# Board_Power.net
KiCad netlist of a schematic drawn in Altium Designer
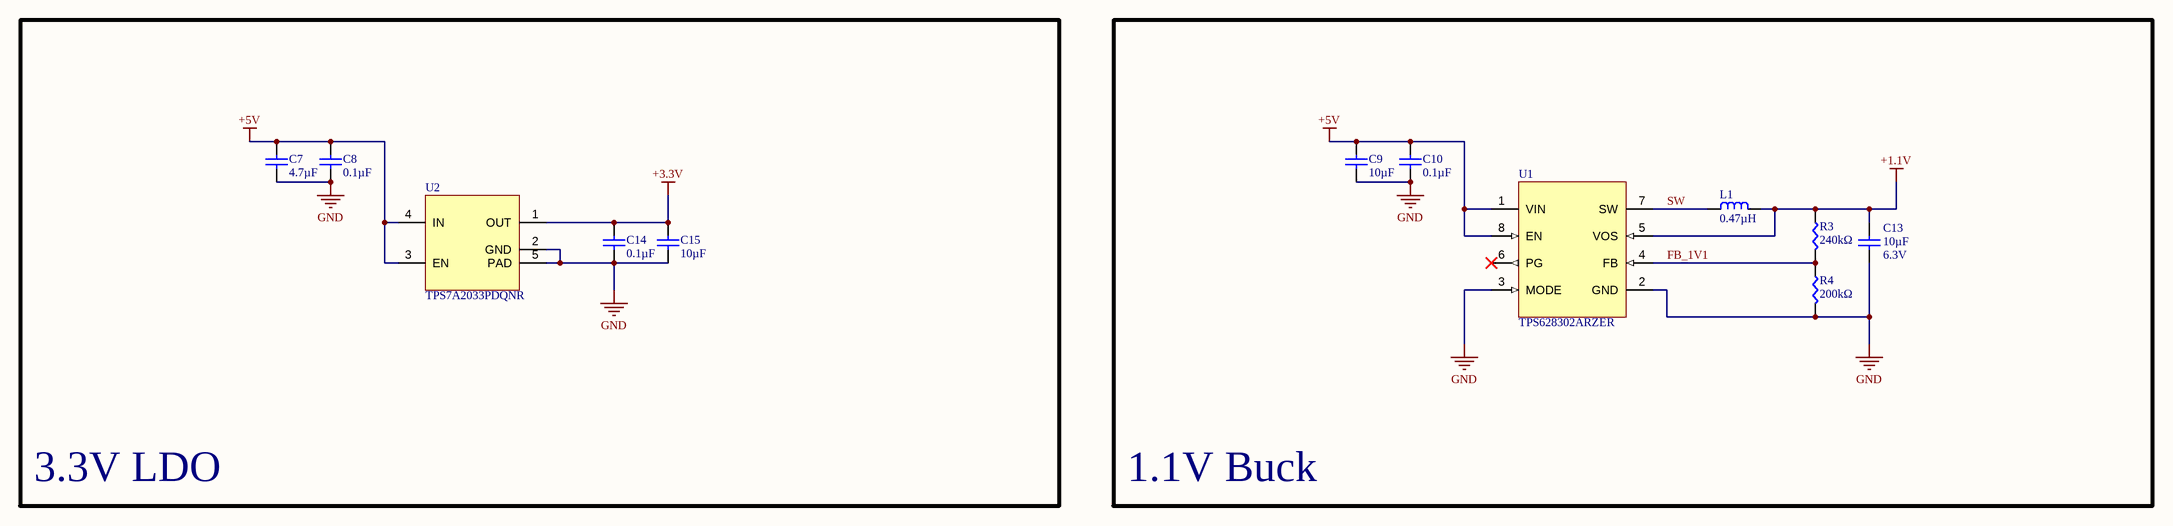
[diagram p0: Board_Power.SchDoc]

(export (version "E")
  (design (tool "Eeschema 10.0.6"))
  (components
    (comp (ref "C7")
      (value "4.7µF")
      (footprint "CAP0603")
      (description "4.7 µF ±10% 25V Ceramic Capacitor X5R 0603 (1608 Metric)")
      (fields (field (name "VOLTAGE") "25V") (field (name "Comment") "GRT21BR61H475KE13L"))
      (libsource (lib "Schlib1") (part "GRM188R61E475KE11D"))
    )
    (comp (ref "C8")
      (value "0.1µF")
      (footprint "CAP0402")
      (description "0.1 µF ±10% 50V Ceramic Capacitor X5R 0402 (1005 Metric)")
      (fields (field (name "VOLTAGE") "50V") (field (name "Comment") "CC0402KRX5R9BB104"))
      (libsource (lib "Schlib1") (part "CC0402KRX5R9BB104"))
    )
    (comp (ref "C9")
      (value "10µF")
      (footprint "CAP0402")
      (description "10 µF ±20% 10V Ceramic Capacitor X5R 0402 (1005 Metric)")
      (fields (field (name "VOLTAGE") "10V") (field (name "Comment") "GRM1555C1H221JA01D"))
      (libsource (lib "Schlib1") (part "GRM155R61A106ME11D"))
    )
    (comp (ref "C10")
      (value "0.1µF")
      (footprint "CAP0402")
      (description "0.1 µF ±10% 50V Ceramic Capacitor X5R 0402 (1005 Metric)")
      (fields (field (name "VOLTAGE") "50V") (field (name "Comment") "CC0402KRX5R9BB104"))
      (libsource (lib "Schlib1") (part "CC0402KRX5R9BB104"))
    )
    (comp (ref "C13")
      (value "10µF")
      (footprint "CAP0402")
      (description "10 µF ±20% 6.3V Ceramic Capacitor X5R 0402 (1005 Metric)")
      (fields (field (name "VOLTAGE") "6.3V") (field (name "Comment") "CL05A106MQ5NUNC"))
      (libsource (lib "Schlib1") (part "CL05A106MQ5NUNC"))
    )
    (comp (ref "C14")
      (value "0.1µF")
      (footprint "CAP0402")
      (description "0.1 µF ±10% 50V Ceramic Capacitor X5R 0402 (1005 Metric)")
      (fields (field (name "VOLTAGE") "50V") (field (name "Comment") "CC0402KRX5R9BB104"))
      (libsource (lib "Schlib1") (part "CC0402KRX5R9BB104"))
    )
    (comp (ref "C15")
      (value "10µF")
      (footprint "CAP0402")
      (description "10 µF ±20% 6.3V Ceramic Capacitor X5R 0402 (1005 Metric)")
      (fields (field (name "VOLTAGE") "6.3V") (field (name "Comment") "CL05A106MQ5NUNC"))
      (libsource (lib "Schlib1") (part "CL05A106MQ5NUNC"))
    )
    (comp (ref "L1")
      (value "0.47µH")
      (footprint "IND0806")
      (description "470 nH Shielded Thin Film Inductor 4.8 A 22mOhm Max 0806 (2016 Metric)")
      (fields (field (name "Comment") "CIGT201610EHR47MNE"))
      (libsource (lib "Schlib1") (part "CIGT201610EHR47MNE"))
    )
    (comp (ref "R3")
      (value "240kΩ")
      (footprint "RES0402")
      (description "240 kOhms ±1% 0.063W, 1/16W Chip Resistor 0402 (1005 Metric) Moisture Resistant Thick Film")
      (fields (field (name "Comment") "RC0402FR-0790K9L"))
      (libsource (lib "Schlib1") (part "RC0402FR-07240KL"))
    )
    (comp (ref "R4")
      (value "200kΩ")
      (footprint "RES0402")
      (description "200 kOhms ±1% 0.1W, 1/10W Chip Resistor 0402 (1005 Metric) Automotive AEC-Q200 Thick Film")
      (fields (field (name "Comment") "ERJ-2RKF3002X"))
      (libsource (lib "Schlib1") (part "ERJ-2RKF2003X"))
    )
    (comp (ref "U1")
      (value "TPS628302ARZER")
      (footprint "WQFN-HR8_RZE_TEX")
      (description "Buck Switching Regulator IC Positive Adjustable 0.5V 1 Output 2A 8-WFDFN")
      (fields (field (name "MANUFACTURER") "Texas Instruments"))
      (libsource (lib "Schlib1") (part "TPS628302ARZER"))
    )
    (comp (ref "U2")
      (value "TPS7A2033PDQNR")
      (footprint "4-X2SON")
      (description "Linear Voltage Regulator IC Positive Fixed 1 Output 300mA 4-X2SON (1x1)")
      (fields (field (name "MANUFACTURER") "Texas Instruments"))
      (libsource (lib "Schlib1") (part "TPS7A2033PDQNR"))
    )
  )
  (nets
    (net (code "1") (name "+1.1V") (class "Default")
      (node (ref "C13") (pin "2") (pinfunction "2_2") (pintype "passive"))
      (node (ref "L1") (pin "2") (pinfunction "2_2") (pintype "passive"))
      (node (ref "R3") (pin "2") (pinfunction "2_2") (pintype "passive"))
      (node (ref "U1") (pin "5") (pinfunction "VOS_5") (pintype "input"))
    )
    (net (code "2") (name "+3.3V") (class "Default")
      (node (ref "C14") (pin "2") (pinfunction "2_2") (pintype "passive"))
      (node (ref "C15") (pin "2") (pinfunction "2_2") (pintype "passive"))
      (node (ref "U2") (pin "1") (pinfunction "OUT_1") (pintype "passive"))
    )
    (net (code "3") (name "+5V") (class "Default")
      (node (ref "C10") (pin "2") (pinfunction "2_2") (pintype "passive"))
      (node (ref "C7") (pin "2") (pinfunction "2_2") (pintype "passive"))
      (node (ref "C8") (pin "2") (pinfunction "2_2") (pintype "passive"))
      (node (ref "C9") (pin "2") (pinfunction "2_2") (pintype "passive"))
      (node (ref "U1") (pin "1") (pinfunction "VIN_1") (pintype "power_in"))
      (node (ref "U1") (pin "8") (pinfunction "EN_8") (pintype "input"))
      (node (ref "U2") (pin "3") (pinfunction "EN_3") (pintype "passive"))
      (node (ref "U2") (pin "4") (pinfunction "IN_4") (pintype "passive"))
    )
    (net (code "4") (name "/FB_1V1") (class "Default")
      (node (ref "R3") (pin "1") (pinfunction "1_1") (pintype "passive"))
      (node (ref "R4") (pin "2") (pinfunction "2_2") (pintype "passive"))
      (node (ref "U1") (pin "4") (pinfunction "FB_4") (pintype "input"))
    )
    (net (code "5") (name "/SW") (class "Default")
      (node (ref "L1") (pin "1") (pinfunction "1_1") (pintype "passive"))
      (node (ref "U1") (pin "7") (pinfunction "SW_7") (pintype "power_in"))
    )
    (net (code "6") (name "GND") (class "Default")
      (node (ref "C10") (pin "1") (pinfunction "1_1") (pintype "passive"))
      (node (ref "C13") (pin "1") (pinfunction "1_1") (pintype "passive"))
      (node (ref "C14") (pin "1") (pinfunction "1_1") (pintype "passive"))
      (node (ref "C15") (pin "1") (pinfunction "1_1") (pintype "passive"))
      (node (ref "C7") (pin "1") (pinfunction "1_1") (pintype "passive"))
      (node (ref "C8") (pin "1") (pinfunction "1_1") (pintype "passive"))
      (node (ref "C9") (pin "1") (pinfunction "1_1") (pintype "passive"))
      (node (ref "R4") (pin "1") (pinfunction "1_1") (pintype "passive"))
      (node (ref "U1") (pin "2") (pinfunction "GND_2") (pintype "passive"))
      (node (ref "U1") (pin "3") (pinfunction "MODE_3") (pintype "input"))
      (node (ref "U2") (pin "2") (pinfunction "GND_2") (pintype "passive"))
      (node (ref "U2") (pin "5") (pinfunction "PAD_5") (pintype "passive"))
    )
    (net (code "7") (name "unconnected-(U1-PG-Pad6)") (class "Default")
      (node (ref "U1") (pin "6") (pinfunction "PG_6") (pintype "output+no_connect"))
    )
  )
)
